# schematic_wemos-temphum_sensor.net
KiCad netlist of a schematic drawn in EAGLE
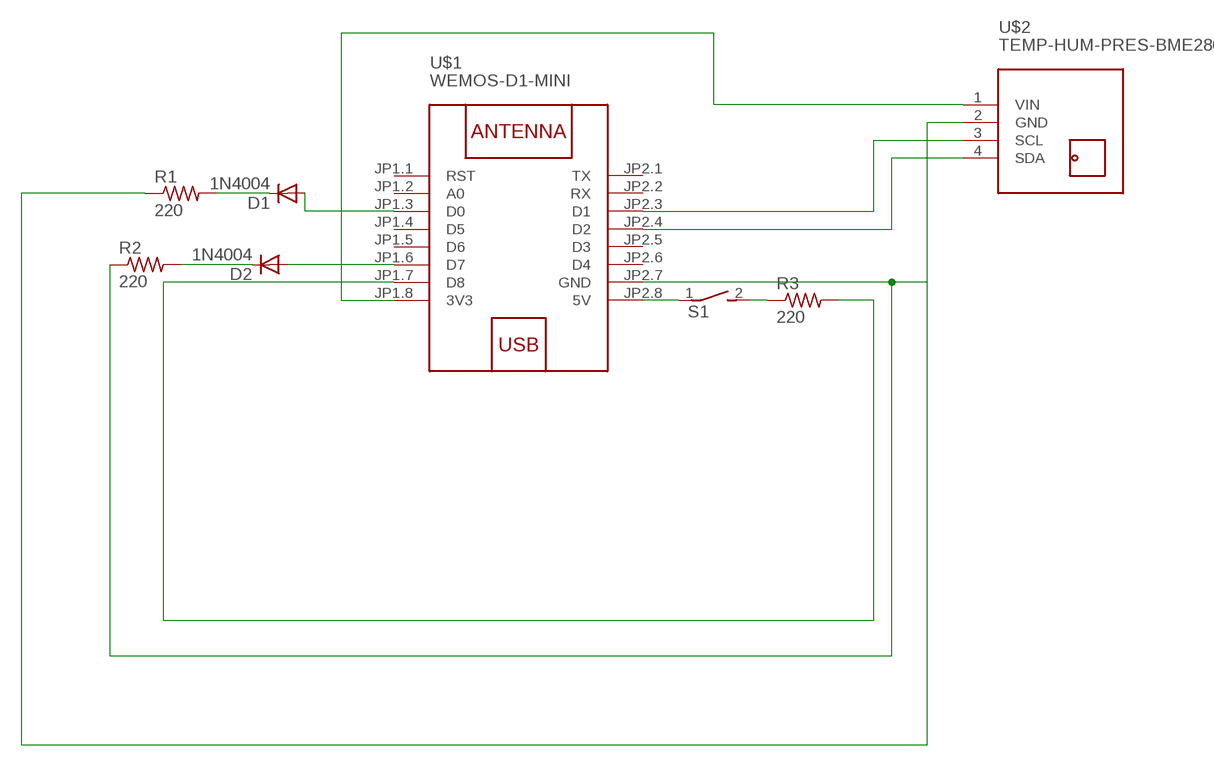
[diagram p0: schematic, sheet 1]

(export (version "E")
  (design (tool "Eeschema 10.0.6"))
  (components
    (comp (ref "D1")
      (value "1N4004")
      (footprint "eagle-import:DO41-10")
      (libsource (lib "eagle-import") (part "1N4004"))
    )
    (comp (ref "D2")
      (value "1N4004")
      (footprint "eagle-import:DO41-10")
      (libsource (lib "eagle-import") (part "1N4004"))
    )
    (comp (ref "R1")
      (value "220")
      (footprint "eagle-import:0207_10")
      (libsource (lib "eagle-import") (part "R-US_0207/10"))
    )
    (comp (ref "R2")
      (value "220")
      (footprint "eagle-import:0207_10")
      (libsource (lib "eagle-import") (part "R-US_0207/10"))
    )
    (comp (ref "R3")
      (value "220")
      (footprint "eagle-import:0207_10")
      (libsource (lib "eagle-import") (part "R-US_0207/10"))
    )
    (comp (ref "S1")
      (value "DS01E")
      (footprint "eagle-import:DS-01")
      (libsource (lib "eagle-import") (part "DS01E"))
    )
    (comp (ref "U$1")
      (value "WEMOS-D1-MINI")
      (footprint "eagle-import:WEMOS-D1-MINI")
      (libsource (lib "eagle-import") (part "WEMOS-D1-MINI"))
    )
    (comp (ref "U$2")
      (value "TEMP-HUM-PRES-BME280")
      (footprint "eagle-import:TEMP-HUM-PRES-BME280")
      (libsource (lib "eagle-import") (part "TEMP-HUM-PRES-BME280"))
    )
  )
  (nets
    (net (code "1") (name "Net-(D1-PadC)") (class "Default")
      (node (ref "D1") (pin "C") (pinfunction "C_C") (pintype "passive"))
      (node (ref "R1") (pin "2") (pinfunction "2_2") (pintype "passive"))
    )
    (net (code "2") (name "Net-(D2-PadC)") (class "Default")
      (node (ref "D2") (pin "C") (pinfunction "C_C") (pintype "passive"))
      (node (ref "R2") (pin "2") (pinfunction "2_2") (pintype "passive"))
    )
    (net (code "3") (name "Net-(R3-Pad1)") (class "Default")
      (node (ref "R3") (pin "1") (pinfunction "1_1") (pintype "passive"))
      (node (ref "S1") (pin "2") (pinfunction "2_2") (pintype "passive"))
    )
    (net (code "4") (name "Net-(U$1-3V3)") (class "Default")
      (node (ref "U$1") (pin "JP1.8") (pinfunction "3V3_JP1.8") (pintype "power_in"))
      (node (ref "U$2") (pin "1") (pinfunction "VIN_1") (pintype "power_in"))
    )
    (net (code "5") (name "Net-(U$1-5V)") (class "Default")
      (node (ref "S1") (pin "1") (pinfunction "1_1") (pintype "passive"))
      (node (ref "U$1") (pin "JP2.8") (pinfunction "5V_JP2.8") (pintype "power_in"))
    )
    (net (code "6") (name "Net-(U$1-D0)") (class "Default")
      (node (ref "D1") (pin "A") (pinfunction "A_A") (pintype "passive"))
      (node (ref "U$1") (pin "JP1.3") (pinfunction "D0_JP1.3") (pintype "bidirectional"))
    )
    (net (code "7") (name "Net-(U$1-D1)") (class "Default")
      (node (ref "U$1") (pin "JP2.3") (pinfunction "D1_JP2.3") (pintype "bidirectional"))
      (node (ref "U$2") (pin "3") (pinfunction "SCL_3") (pintype "bidirectional"))
    )
    (net (code "8") (name "Net-(U$1-D2)") (class "Default")
      (node (ref "U$1") (pin "JP2.4") (pinfunction "D2_JP2.4") (pintype "bidirectional"))
      (node (ref "U$2") (pin "4") (pinfunction "SDA_4") (pintype "bidirectional"))
    )
    (net (code "9") (name "Net-(U$1-D7)") (class "Default")
      (node (ref "D2") (pin "A") (pinfunction "A_A") (pintype "passive"))
      (node (ref "U$1") (pin "JP1.6") (pinfunction "D7_JP1.6") (pintype "bidirectional"))
    )
    (net (code "10") (name "Net-(U$1-D8)") (class "Default")
      (node (ref "R3") (pin "2") (pinfunction "2_2") (pintype "passive"))
      (node (ref "U$1") (pin "JP1.7") (pinfunction "D8_JP1.7") (pintype "bidirectional"))
    )
    (net (code "11") (name "Net-(U$1-GND)") (class "Default")
      (node (ref "R1") (pin "1") (pinfunction "1_1") (pintype "passive"))
      (node (ref "R2") (pin "1") (pinfunction "1_1") (pintype "passive"))
      (node (ref "U$1") (pin "JP2.7") (pinfunction "GND_JP2.7") (pintype "power_in"))
      (node (ref "U$2") (pin "2") (pinfunction "GND_2") (pintype "power_in"))
    )
    (net (code "12") (name "unconnected-(U$1-A0-PadJP1.2)") (class "Default")
      (node (ref "U$1") (pin "JP1.2") (pinfunction "A0_JP1.2") (pintype "bidirectional"))
    )
    (net (code "13") (name "unconnected-(U$1-D3-PadJP2.5)") (class "Default")
      (node (ref "U$1") (pin "JP2.5") (pinfunction "D3_JP2.5") (pintype "bidirectional"))
    )
    (net (code "14") (name "unconnected-(U$1-D4-PadJP2.6)") (class "Default")
      (node (ref "U$1") (pin "JP2.6") (pinfunction "D4_JP2.6") (pintype "bidirectional"))
    )
    (net (code "15") (name "unconnected-(U$1-D5-PadJP1.4)") (class "Default")
      (node (ref "U$1") (pin "JP1.4") (pinfunction "D5_JP1.4") (pintype "bidirectional"))
    )
    (net (code "16") (name "unconnected-(U$1-D6-PadJP1.5)") (class "Default")
      (node (ref "U$1") (pin "JP1.5") (pinfunction "D6_JP1.5") (pintype "bidirectional"))
    )
    (net (code "17") (name "unconnected-(U$1-RST-PadJP1.1)") (class "Default")
      (node (ref "U$1") (pin "JP1.1") (pinfunction "RST_JP1.1") (pintype "bidirectional"))
    )
    (net (code "18") (name "unconnected-(U$1-RX-PadJP2.2)") (class "Default")
      (node (ref "U$1") (pin "JP2.2") (pinfunction "RX_JP2.2") (pintype "bidirectional"))
    )
    (net (code "19") (name "unconnected-(U$1-TX-PadJP2.1)") (class "Default")
      (node (ref "U$1") (pin "JP2.1") (pinfunction "TX_JP2.1") (pintype "bidirectional"))
    )
  )
)
